# STM32L0.net
KiCad netlist of a schematic drawn in EAGLE
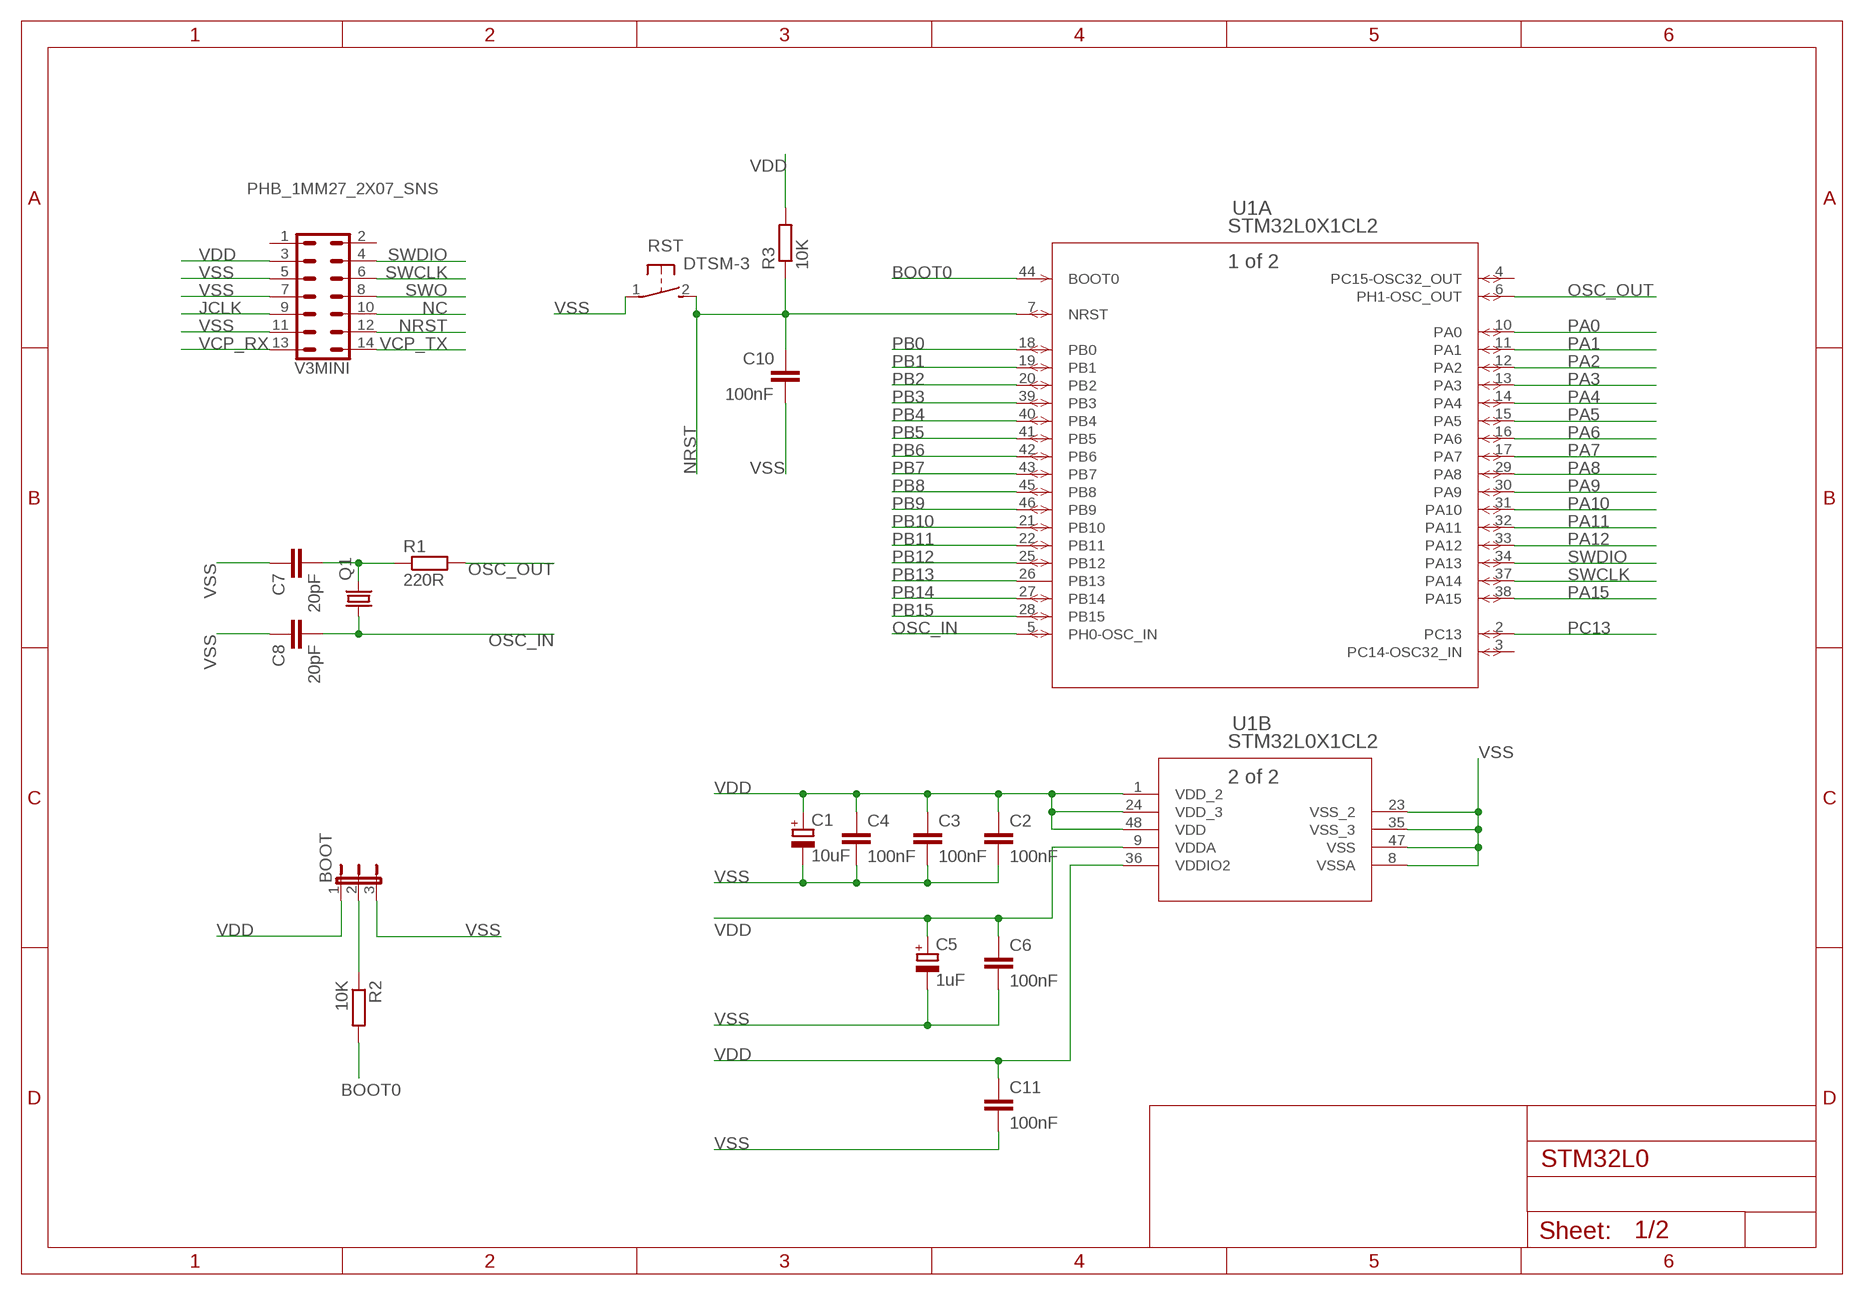
[diagram p0: schematic, sheet 1]
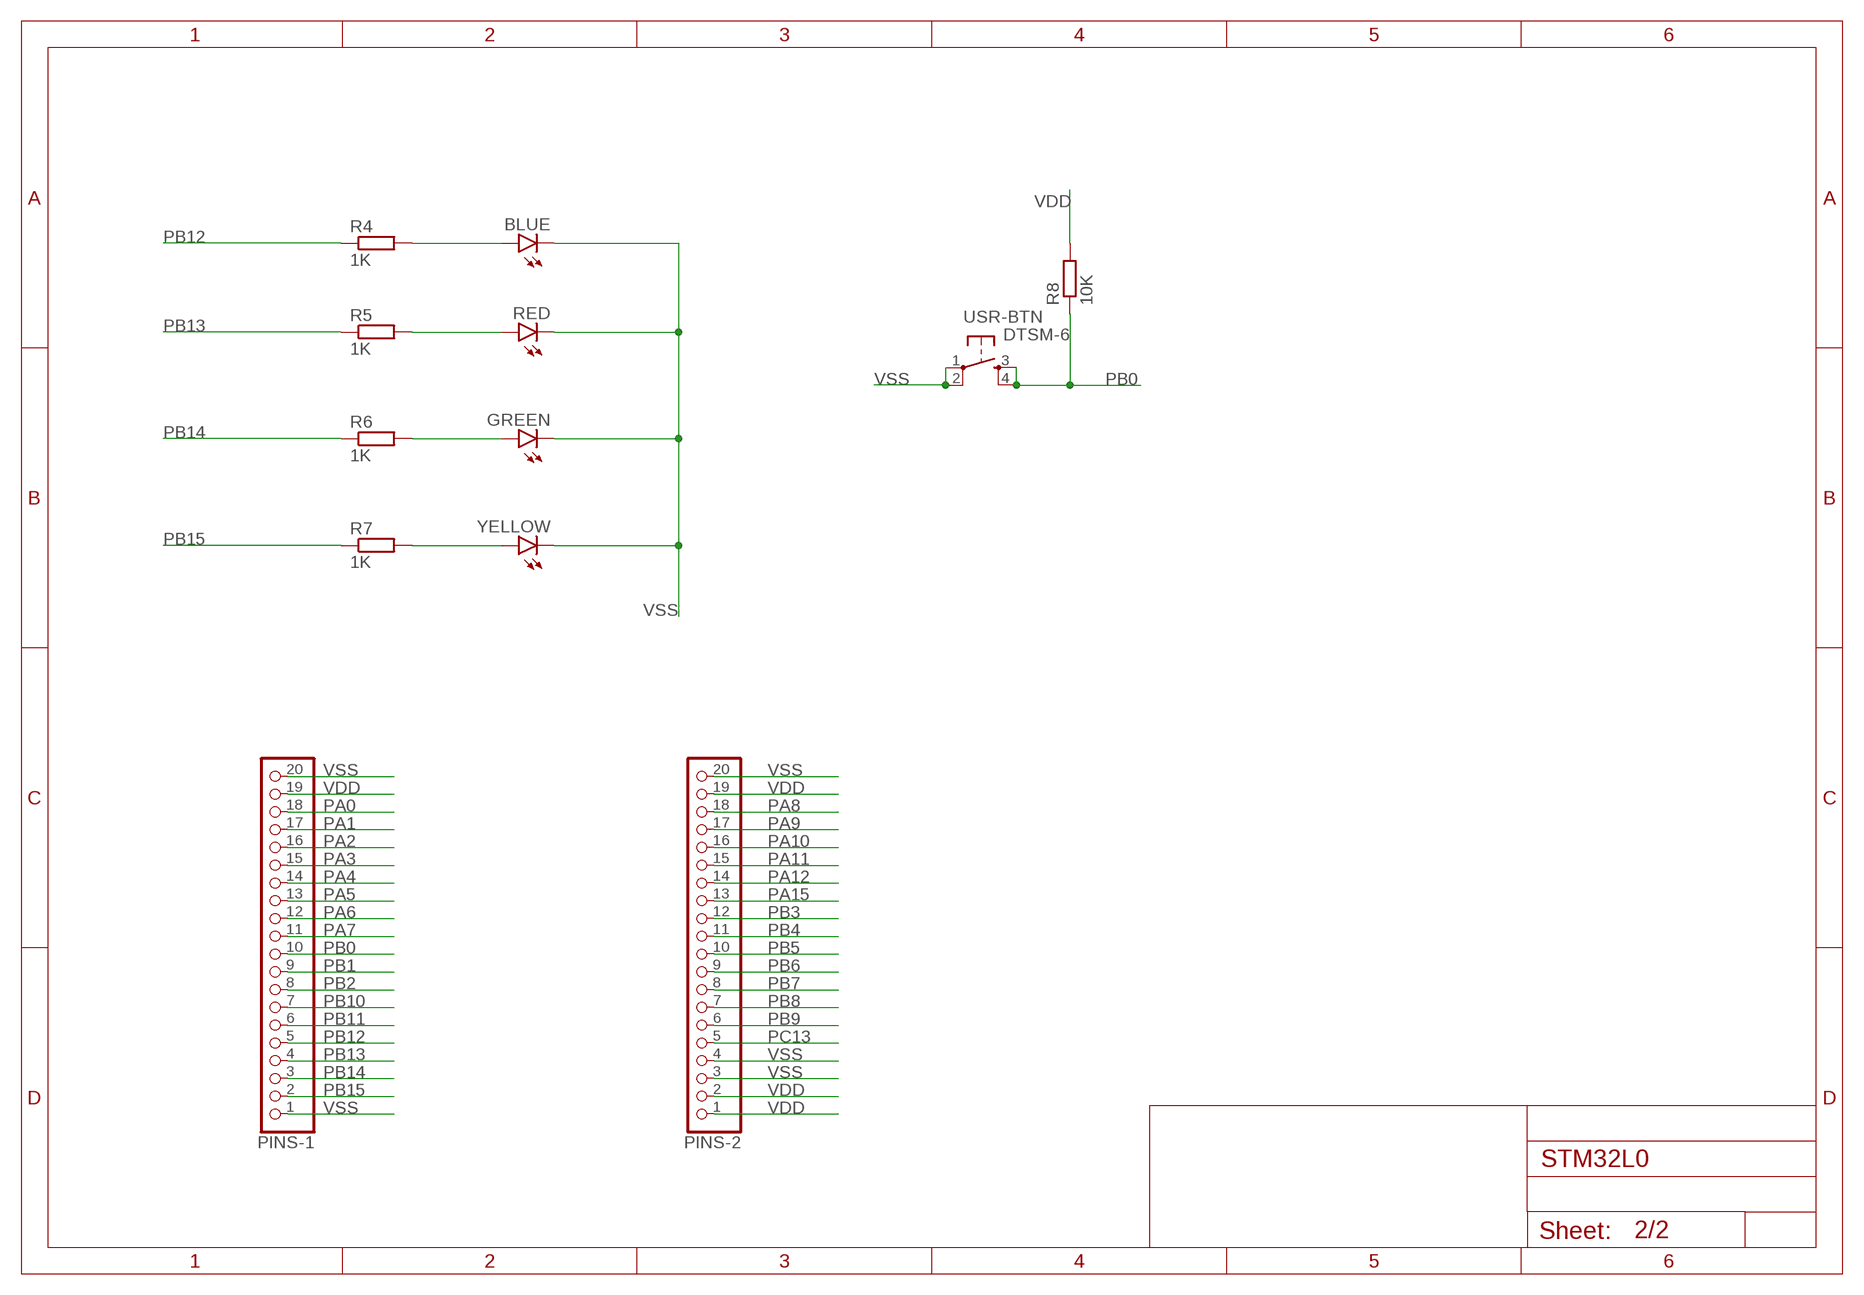
[diagram p1: schematic, sheet 2]

(export (version "E")
  (design (tool "Eeschema 10.0.6"))
  (components
    (comp (ref "BOOT")
      (value "JP2E")
      (footprint "eagle-import:JP2")
      (libsource (lib "eagle-import") (part "JP2E"))
    )
    (comp (ref "C1")
      (value "10uF")
      (footprint "eagle-import:SMC_A")
      (libsource (lib "eagle-import") (part "CPOL-EUSMCA"))
    )
    (comp (ref "C2")
      (value "100nF")
      (footprint "eagle-import:C0805")
      (libsource (lib "eagle-import") (part "C-EUC0805"))
    )
    (comp (ref "C3")
      (value "100nF")
      (footprint "eagle-import:C0805")
      (libsource (lib "eagle-import") (part "C-EUC0805"))
    )
    (comp (ref "C4")
      (value "100nF")
      (footprint "eagle-import:C0805")
      (libsource (lib "eagle-import") (part "C-EUC0805"))
    )
    (comp (ref "C5")
      (value "1uF")
      (footprint "eagle-import:SMC_A")
      (libsource (lib "eagle-import") (part "CPOL-EUSMCA"))
    )
    (comp (ref "C6")
      (value "100nF")
      (footprint "eagle-import:C0805")
      (libsource (lib "eagle-import") (part "C-EUC0805"))
    )
    (comp (ref "C7")
      (value "20pF")
      (footprint "eagle-import:C0805")
      (libsource (lib "eagle-import") (part "C-EUC0805"))
    )
    (comp (ref "C8")
      (value "20pF")
      (footprint "eagle-import:C0805")
      (libsource (lib "eagle-import") (part "C-EUC0805"))
    )
    (comp (ref "C10")
      (value "100nF")
      (footprint "eagle-import:C0805")
      (libsource (lib "eagle-import") (part "C-EUC0805"))
    )
    (comp (ref "C11")
      (value "100nF")
      (footprint "eagle-import:C0805")
      (libsource (lib "eagle-import") (part "C-EUC0805"))
    )
    (comp (ref "Q1")
      (value "CRYSTALSM49")
      (footprint "eagle-import:SM49")
      (libsource (lib "eagle-import") (part "CRYSTALSM49"))
    )
    (comp (ref "R1")
      (value "220R")
      (footprint "eagle-import:R0805")
      (libsource (lib "eagle-import") (part "R-EU_R0805"))
    )
    (comp (ref "R2")
      (value "10K")
      (footprint "eagle-import:R0805")
      (libsource (lib "eagle-import") (part "R-EU_R0805"))
    )
    (comp (ref "R3")
      (value "10K")
      (footprint "eagle-import:R0805")
      (libsource (lib "eagle-import") (part "R-EU_R0805"))
    )
    (comp (ref "RST")
      (value "DTSM-3")
      (footprint "eagle-import:DTSM-3")
      (libsource (lib "eagle-import") (part "DTSM-3"))
    )
    (comp (ref "U1")
      (value "STM32L0X1CL2")
      (footprint "eagle-import:LQFP48-7X7MM")
      (fields (field (name "COPYRIGHT") "Copyright (C) 2016 Accelerated Designs. All rights reserved"))
      (libsource (lib "eagle-import") (part "STM32L0X1CL2"))
    )
    (comp (ref "V3MINI")
      (value "PHB_1MM27_2X07_SNS")
      (footprint "eagle-import:PHB_1MM27_2X07_SNS")
      (libsource (lib "eagle-import") (part "PHB_1MM27_2X07_SNS"))
    )
    (comp (ref "BLUE")
      (value "LEDCHIPLED_0805")
      (footprint "eagle-import:CHIPLED_0805")
      (libsource (lib "eagle-import") (part "LEDCHIPLED_0805"))
    )
    (comp (ref "GREEN")
      (value "LEDCHIPLED_0805")
      (footprint "eagle-import:CHIPLED_0805")
      (libsource (lib "eagle-import") (part "LEDCHIPLED_0805"))
    )
    (comp (ref "PINS-1")
      (value "PINHD-1X20")
      (footprint "eagle-import:1X20")
      (libsource (lib "eagle-import") (part "PINHD-1X20"))
    )
    (comp (ref "PINS-2")
      (value "PINHD-1X20")
      (footprint "eagle-import:1X20")
      (libsource (lib "eagle-import") (part "PINHD-1X20"))
    )
    (comp (ref "R4")
      (value "1K")
      (footprint "eagle-import:R0805")
      (libsource (lib "eagle-import") (part "R-EU_R0805"))
    )
    (comp (ref "R5")
      (value "1K")
      (footprint "eagle-import:R0805")
      (libsource (lib "eagle-import") (part "R-EU_R0805"))
    )
    (comp (ref "R6")
      (value "1K")
      (footprint "eagle-import:R0805")
      (libsource (lib "eagle-import") (part "R-EU_R0805"))
    )
    (comp (ref "R7")
      (value "1K")
      (footprint "eagle-import:R0805")
      (libsource (lib "eagle-import") (part "R-EU_R0805"))
    )
    (comp (ref "R8")
      (value "10K")
      (footprint "eagle-import:R0805")
      (libsource (lib "eagle-import") (part "R-EU_R0805"))
    )
    (comp (ref "RED")
      (value "LEDCHIPLED_0805")
      (footprint "eagle-import:CHIPLED_0805")
      (libsource (lib "eagle-import") (part "LEDCHIPLED_0805"))
    )
    (comp (ref "USR-BTN")
      (value "DTSM-6")
      (footprint "eagle-import:DTSM-6")
      (libsource (lib "eagle-import") (part "DTSM-6"))
    )
    (comp (ref "YELLOW")
      (value "LEDCHIPLED_0805")
      (footprint "eagle-import:CHIPLED_0805")
      (libsource (lib "eagle-import") (part "LEDCHIPLED_0805"))
    )
  )
  (nets
    (net (code "1") (name "BOOT0") (class "Default")
      (node (ref "R2") (pin "2") (pinfunction "2_2") (pintype "passive"))
      (node (ref "U1") (pin "44") (pinfunction "BOOT0_44") (pintype "input"))
    )
    (net (code "2") (name "JCLK") (class "Default")
      (node (ref "V3MINI") (pin "9") (pinfunction "9_9") (pintype "passive"))
    )
    (net (code "3") (name "NC") (class "Default")
      (node (ref "V3MINI") (pin "10") (pinfunction "10_10") (pintype "passive"))
    )
    (net (code "4") (name "NRST") (class "Default")
      (node (ref "C10") (pin "1") (pinfunction "1_1") (pintype "passive"))
      (node (ref "R3") (pin "1") (pinfunction "1_1") (pintype "passive"))
      (node (ref "RST") (pin "2") (pinfunction "2_2") (pintype "passive"))
      (node (ref "U1") (pin "7") (pinfunction "NRST_7") (pintype "bidirectional"))
      (node (ref "V3MINI") (pin "12") (pinfunction "12_12") (pintype "passive"))
    )
    (net (code "5") (name "Net-(BLUE-PadA)") (class "Default")
      (node (ref "BLUE") (pin "A") (pinfunction "A_A") (pintype "passive"))
      (node (ref "R4") (pin "2") (pinfunction "2_2") (pintype "passive"))
    )
    (net (code "6") (name "Net-(BOOT-Pad2)") (class "Default")
      (node (ref "BOOT") (pin "2") (pinfunction "2_2") (pintype "passive"))
      (node (ref "R2") (pin "1") (pinfunction "1_1") (pintype "passive"))
    )
    (net (code "7") (name "Net-(C7-Pad2)") (class "Default")
      (node (ref "C7") (pin "2") (pinfunction "2_2") (pintype "passive"))
      (node (ref "Q1") (pin "2") (pinfunction "2_2") (pintype "passive"))
      (node (ref "R1") (pin "1") (pinfunction "1_1") (pintype "passive"))
    )
    (net (code "8") (name "Net-(GREEN-PadA)") (class "Default")
      (node (ref "GREEN") (pin "A") (pinfunction "A_A") (pintype "passive"))
      (node (ref "R6") (pin "2") (pinfunction "2_2") (pintype "passive"))
    )
    (net (code "9") (name "Net-(R5-Pad2)") (class "Default")
      (node (ref "R5") (pin "2") (pinfunction "2_2") (pintype "passive"))
      (node (ref "RED") (pin "A") (pinfunction "A_A") (pintype "passive"))
    )
    (net (code "10") (name "Net-(R7-Pad2)") (class "Default")
      (node (ref "R7") (pin "2") (pinfunction "2_2") (pintype "passive"))
      (node (ref "YELLOW") (pin "A") (pinfunction "A_A") (pintype "passive"))
    )
    (net (code "11") (name "OSC_IN") (class "Default")
      (node (ref "C8") (pin "2") (pinfunction "2_2") (pintype "passive"))
      (node (ref "Q1") (pin "1") (pinfunction "1_1") (pintype "passive"))
      (node (ref "U1") (pin "5") (pinfunction "PH0-OSC_IN_5") (pintype "bidirectional"))
    )
    (net (code "12") (name "OSC_OUT") (class "Default")
      (node (ref "R1") (pin "2") (pinfunction "2_2") (pintype "passive"))
      (node (ref "U1") (pin "6") (pinfunction "PH1-OSC_OUT_6") (pintype "bidirectional"))
    )
    (net (code "13") (name "PA0") (class "Default")
      (node (ref "PINS-1") (pin "18") (pinfunction "18_18") (pintype "passive"))
      (node (ref "U1") (pin "10") (pinfunction "PA0_10") (pintype "bidirectional"))
    )
    (net (code "14") (name "PA1") (class "Default")
      (node (ref "PINS-1") (pin "17") (pinfunction "17_17") (pintype "passive"))
      (node (ref "U1") (pin "11") (pinfunction "PA1_11") (pintype "bidirectional"))
    )
    (net (code "15") (name "PA2") (class "Default")
      (node (ref "PINS-1") (pin "16") (pinfunction "16_16") (pintype "passive"))
      (node (ref "U1") (pin "12") (pinfunction "PA2_12") (pintype "bidirectional"))
    )
    (net (code "16") (name "PA3") (class "Default")
      (node (ref "PINS-1") (pin "15") (pinfunction "15_15") (pintype "passive"))
      (node (ref "U1") (pin "13") (pinfunction "PA3_13") (pintype "bidirectional"))
    )
    (net (code "17") (name "PA4") (class "Default")
      (node (ref "PINS-1") (pin "14") (pinfunction "14_14") (pintype "passive"))
      (node (ref "U1") (pin "14") (pinfunction "PA4_14") (pintype "bidirectional"))
    )
    (net (code "18") (name "PA5") (class "Default")
      (node (ref "PINS-1") (pin "13") (pinfunction "13_13") (pintype "passive"))
      (node (ref "U1") (pin "15") (pinfunction "PA5_15") (pintype "bidirectional"))
    )
    (net (code "19") (name "PA6") (class "Default")
      (node (ref "PINS-1") (pin "12") (pinfunction "12_12") (pintype "passive"))
      (node (ref "U1") (pin "16") (pinfunction "PA6_16") (pintype "bidirectional"))
    )
    (net (code "20") (name "PA7") (class "Default")
      (node (ref "PINS-1") (pin "11") (pinfunction "11_11") (pintype "passive"))
      (node (ref "U1") (pin "17") (pinfunction "PA7_17") (pintype "bidirectional"))
    )
    (net (code "21") (name "PA8") (class "Default")
      (node (ref "PINS-2") (pin "18") (pinfunction "18_18") (pintype "passive"))
      (node (ref "U1") (pin "29") (pinfunction "PA8_29") (pintype "bidirectional"))
    )
    (net (code "22") (name "PA9") (class "Default")
      (node (ref "PINS-2") (pin "17") (pinfunction "17_17") (pintype "passive"))
      (node (ref "U1") (pin "30") (pinfunction "PA9_30") (pintype "bidirectional"))
    )
    (net (code "23") (name "PA10") (class "Default")
      (node (ref "PINS-2") (pin "16") (pinfunction "16_16") (pintype "passive"))
      (node (ref "U1") (pin "31") (pinfunction "PA10_31") (pintype "bidirectional"))
    )
    (net (code "24") (name "PA11") (class "Default")
      (node (ref "PINS-2") (pin "15") (pinfunction "15_15") (pintype "passive"))
      (node (ref "U1") (pin "32") (pinfunction "PA11_32") (pintype "bidirectional"))
    )
    (net (code "25") (name "PA12") (class "Default")
      (node (ref "PINS-2") (pin "14") (pinfunction "14_14") (pintype "passive"))
      (node (ref "U1") (pin "33") (pinfunction "PA12_33") (pintype "bidirectional"))
    )
    (net (code "26") (name "PA15") (class "Default")
      (node (ref "PINS-2") (pin "13") (pinfunction "13_13") (pintype "passive"))
      (node (ref "U1") (pin "38") (pinfunction "PA15_38") (pintype "bidirectional"))
    )
    (net (code "27") (name "PB0") (class "Default")
      (node (ref "PINS-1") (pin "10") (pinfunction "10_10") (pintype "passive"))
      (node (ref "R8") (pin "1") (pinfunction "1_1") (pintype "passive"))
      (node (ref "U1") (pin "18") (pinfunction "PB0_18") (pintype "bidirectional"))
      (node (ref "USR-BTN") (pin "3") (pinfunction "3_3") (pintype "passive"))
      (node (ref "USR-BTN") (pin "4") (pinfunction "4_4") (pintype "passive"))
    )
    (net (code "28") (name "PB1") (class "Default")
      (node (ref "PINS-1") (pin "9") (pinfunction "9_9") (pintype "passive"))
      (node (ref "U1") (pin "19") (pinfunction "PB1_19") (pintype "bidirectional"))
    )
    (net (code "29") (name "PB2") (class "Default")
      (node (ref "PINS-1") (pin "8") (pinfunction "8_8") (pintype "passive"))
      (node (ref "U1") (pin "20") (pinfunction "PB2_20") (pintype "bidirectional"))
    )
    (net (code "30") (name "PB3") (class "Default")
      (node (ref "PINS-2") (pin "12") (pinfunction "12_12") (pintype "passive"))
      (node (ref "U1") (pin "39") (pinfunction "PB3_39") (pintype "bidirectional"))
    )
    (net (code "31") (name "PB4") (class "Default")
      (node (ref "PINS-2") (pin "11") (pinfunction "11_11") (pintype "passive"))
      (node (ref "U1") (pin "40") (pinfunction "PB4_40") (pintype "bidirectional"))
    )
    (net (code "32") (name "PB5") (class "Default")
      (node (ref "PINS-2") (pin "10") (pinfunction "10_10") (pintype "passive"))
      (node (ref "U1") (pin "41") (pinfunction "PB5_41") (pintype "bidirectional"))
    )
    (net (code "33") (name "PB6") (class "Default")
      (node (ref "PINS-2") (pin "9") (pinfunction "9_9") (pintype "passive"))
      (node (ref "U1") (pin "42") (pinfunction "PB6_42") (pintype "bidirectional"))
    )
    (net (code "34") (name "PB7") (class "Default")
      (node (ref "PINS-2") (pin "8") (pinfunction "8_8") (pintype "passive"))
      (node (ref "U1") (pin "43") (pinfunction "PB7_43") (pintype "bidirectional"))
    )
    (net (code "35") (name "PB8") (class "Default")
      (node (ref "PINS-2") (pin "7") (pinfunction "7_7") (pintype "passive"))
      (node (ref "U1") (pin "45") (pinfunction "PB8_45") (pintype "bidirectional"))
    )
    (net (code "36") (name "PB9") (class "Default")
      (node (ref "PINS-2") (pin "6") (pinfunction "6_6") (pintype "passive"))
      (node (ref "U1") (pin "46") (pinfunction "PB9_46") (pintype "bidirectional"))
    )
    (net (code "37") (name "PB10") (class "Default")
      (node (ref "PINS-1") (pin "7") (pinfunction "7_7") (pintype "passive"))
      (node (ref "U1") (pin "21") (pinfunction "PB10_21") (pintype "bidirectional"))
    )
    (net (code "38") (name "PB11") (class "Default")
      (node (ref "PINS-1") (pin "6") (pinfunction "6_6") (pintype "passive"))
      (node (ref "U1") (pin "22") (pinfunction "PB11_22") (pintype "bidirectional"))
    )
    (net (code "39") (name "PB12") (class "Default")
      (node (ref "PINS-1") (pin "5") (pinfunction "5_5") (pintype "passive"))
      (node (ref "R4") (pin "1") (pinfunction "1_1") (pintype "passive"))
      (node (ref "U1") (pin "25") (pinfunction "PB12_25") (pintype "bidirectional"))
    )
    (net (code "40") (name "PB13") (class "Default")
      (node (ref "PINS-1") (pin "4") (pinfunction "4_4") (pintype "passive"))
      (node (ref "R5") (pin "1") (pinfunction "1_1") (pintype "passive"))
      (node (ref "U1") (pin "26") (pinfunction "PB13_26") (pintype "bidirectional"))
    )
    (net (code "41") (name "PB14") (class "Default")
      (node (ref "PINS-1") (pin "3") (pinfunction "3_3") (pintype "passive"))
      (node (ref "R6") (pin "1") (pinfunction "1_1") (pintype "passive"))
      (node (ref "U1") (pin "27") (pinfunction "PB14_27") (pintype "bidirectional"))
    )
    (net (code "42") (name "PB15") (class "Default")
      (node (ref "PINS-1") (pin "2") (pinfunction "2_2") (pintype "passive"))
      (node (ref "R7") (pin "1") (pinfunction "1_1") (pintype "passive"))
      (node (ref "U1") (pin "28") (pinfunction "PB15_28") (pintype "bidirectional"))
    )
    (net (code "43") (name "PC13") (class "Default")
      (node (ref "PINS-2") (pin "5") (pinfunction "5_5") (pintype "passive"))
      (node (ref "U1") (pin "2") (pinfunction "PC13_2") (pintype "bidirectional"))
    )
    (net (code "44") (name "SWCLK") (class "Default")
      (node (ref "U1") (pin "37") (pinfunction "PA14_37") (pintype "bidirectional"))
      (node (ref "V3MINI") (pin "6") (pinfunction "6_6") (pintype "passive"))
    )
    (net (code "45") (name "SWDIO") (class "Default")
      (node (ref "U1") (pin "34") (pinfunction "PA13_34") (pintype "bidirectional"))
      (node (ref "V3MINI") (pin "4") (pinfunction "4_4") (pintype "passive"))
    )
    (net (code "46") (name "SWO") (class "Default")
      (node (ref "V3MINI") (pin "8") (pinfunction "8_8") (pintype "passive"))
    )
    (net (code "47") (name "VCP_RX") (class "Default")
      (node (ref "V3MINI") (pin "13") (pinfunction "13_13") (pintype "passive"))
    )
    (net (code "48") (name "VCP_TX") (class "Default")
      (node (ref "V3MINI") (pin "14") (pinfunction "14_14") (pintype "passive"))
    )
    (net (code "49") (name "VDD") (class "Default")
      (node (ref "BOOT") (pin "1") (pinfunction "1_1") (pintype "passive"))
      (node (ref "C1") (pin "+") (pinfunction "+_+") (pintype "passive"))
      (node (ref "C11") (pin "1") (pinfunction "1_1") (pintype "passive"))
      (node (ref "C2") (pin "1") (pinfunction "1_1") (pintype "passive"))
      (node (ref "C3") (pin "1") (pinfunction "1_1") (pintype "passive"))
      (node (ref "C4") (pin "1") (pinfunction "1_1") (pintype "passive"))
      (node (ref "C5") (pin "+") (pinfunction "+_+") (pintype "passive"))
      (node (ref "C6") (pin "1") (pinfunction "1_1") (pintype "passive"))
      (node (ref "PINS-1") (pin "19") (pinfunction "19_19") (pintype "passive"))
      (node (ref "PINS-2") (pin "1") (pinfunction "1_1") (pintype "passive"))
      (node (ref "PINS-2") (pin "19") (pinfunction "19_19") (pintype "passive"))
      (node (ref "PINS-2") (pin "2") (pinfunction "2_2") (pintype "passive"))
      (node (ref "R3") (pin "2") (pinfunction "2_2") (pintype "passive"))
      (node (ref "R8") (pin "2") (pinfunction "2_2") (pintype "passive"))
      (node (ref "U1") (pin "1") (pinfunction "VDD_2_1") (pintype "power_in"))
      (node (ref "U1") (pin "24") (pinfunction "VDD_3_24") (pintype "power_in"))
      (node (ref "U1") (pin "36") (pinfunction "VDDIO2_36") (pintype "power_in"))
      (node (ref "U1") (pin "48") (pinfunction "VDD_48") (pintype "power_in"))
      (node (ref "U1") (pin "9") (pinfunction "VDDA_9") (pintype "power_in"))
      (node (ref "V3MINI") (pin "3") (pinfunction "3_3") (pintype "passive"))
    )
    (net (code "50") (name "VSS") (class "Default")
      (node (ref "BLUE") (pin "C") (pinfunction "C_C") (pintype "passive"))
      (node (ref "BOOT") (pin "3") (pinfunction "3_3") (pintype "passive"))
      (node (ref "C1") (pin "-") (pinfunction "-_-") (pintype "passive"))
      (node (ref "C10") (pin "2") (pinfunction "2_2") (pintype "passive"))
      (node (ref "C11") (pin "2") (pinfunction "2_2") (pintype "passive"))
      (node (ref "C2") (pin "2") (pinfunction "2_2") (pintype "passive"))
      (node (ref "C3") (pin "2") (pinfunction "2_2") (pintype "passive"))
      (node (ref "C4") (pin "2") (pinfunction "2_2") (pintype "passive"))
      (node (ref "C5") (pin "-") (pinfunction "-_-") (pintype "passive"))
      (node (ref "C6") (pin "2") (pinfunction "2_2") (pintype "passive"))
      (node (ref "C7") (pin "1") (pinfunction "1_1") (pintype "passive"))
      (node (ref "C8") (pin "1") (pinfunction "1_1") (pintype "passive"))
      (node (ref "GREEN") (pin "C") (pinfunction "C_C") (pintype "passive"))
      (node (ref "PINS-1") (pin "1") (pinfunction "1_1") (pintype "passive"))
      (node (ref "PINS-1") (pin "20") (pinfunction "20_20") (pintype "passive"))
      (node (ref "PINS-2") (pin "20") (pinfunction "20_20") (pintype "passive"))
      (node (ref "PINS-2") (pin "3") (pinfunction "3_3") (pintype "passive"))
      (node (ref "PINS-2") (pin "4") (pinfunction "4_4") (pintype "passive"))
      (node (ref "RED") (pin "C") (pinfunction "C_C") (pintype "passive"))
      (node (ref "RST") (pin "1") (pinfunction "1_1") (pintype "passive"))
      (node (ref "U1") (pin "23") (pinfunction "VSS_2_23") (pintype "power_in"))
      (node (ref "U1") (pin "35") (pinfunction "VSS_3_35") (pintype "power_in"))
      (node (ref "U1") (pin "47") (pinfunction "VSS_47") (pintype "power_in"))
      (node (ref "U1") (pin "8") (pinfunction "VSSA_8") (pintype "power_in"))
      (node (ref "USR-BTN") (pin "1") (pinfunction "1_1") (pintype "passive"))
      (node (ref "USR-BTN") (pin "2") (pinfunction "2_2") (pintype "passive"))
      (node (ref "V3MINI") (pin "11") (pinfunction "11_11") (pintype "passive"))
      (node (ref "V3MINI") (pin "5") (pinfunction "5_5") (pintype "passive"))
      (node (ref "V3MINI") (pin "7") (pinfunction "7_7") (pintype "passive"))
      (node (ref "YELLOW") (pin "C") (pinfunction "C_C") (pintype "passive"))
    )
    (net (code "51") (name "unconnected-(U1A-PC14-OSC32_IN-Pad3)") (class "Default")
      (node (ref "U1") (pin "3") (pinfunction "PC14-OSC32_IN_3") (pintype "bidirectional"))
    )
    (net (code "52") (name "unconnected-(U1A-PC15-OSC32_OUT-Pad4)") (class "Default")
      (node (ref "U1") (pin "4") (pinfunction "PC15-OSC32_OUT_4") (pintype "bidirectional"))
    )
    (net (code "53") (name "unconnected-(V3MINI-Pad1)") (class "Default")
      (node (ref "V3MINI") (pin "1") (pinfunction "1_1") (pintype "passive"))
    )
    (net (code "54") (name "unconnected-(V3MINI-Pad2)") (class "Default")
      (node (ref "V3MINI") (pin "2") (pinfunction "2_2") (pintype "passive"))
    )
  )
)
